# Stepper_Driver_Sheet1.net
KiCad netlist of a schematic drawn in Altium Designer
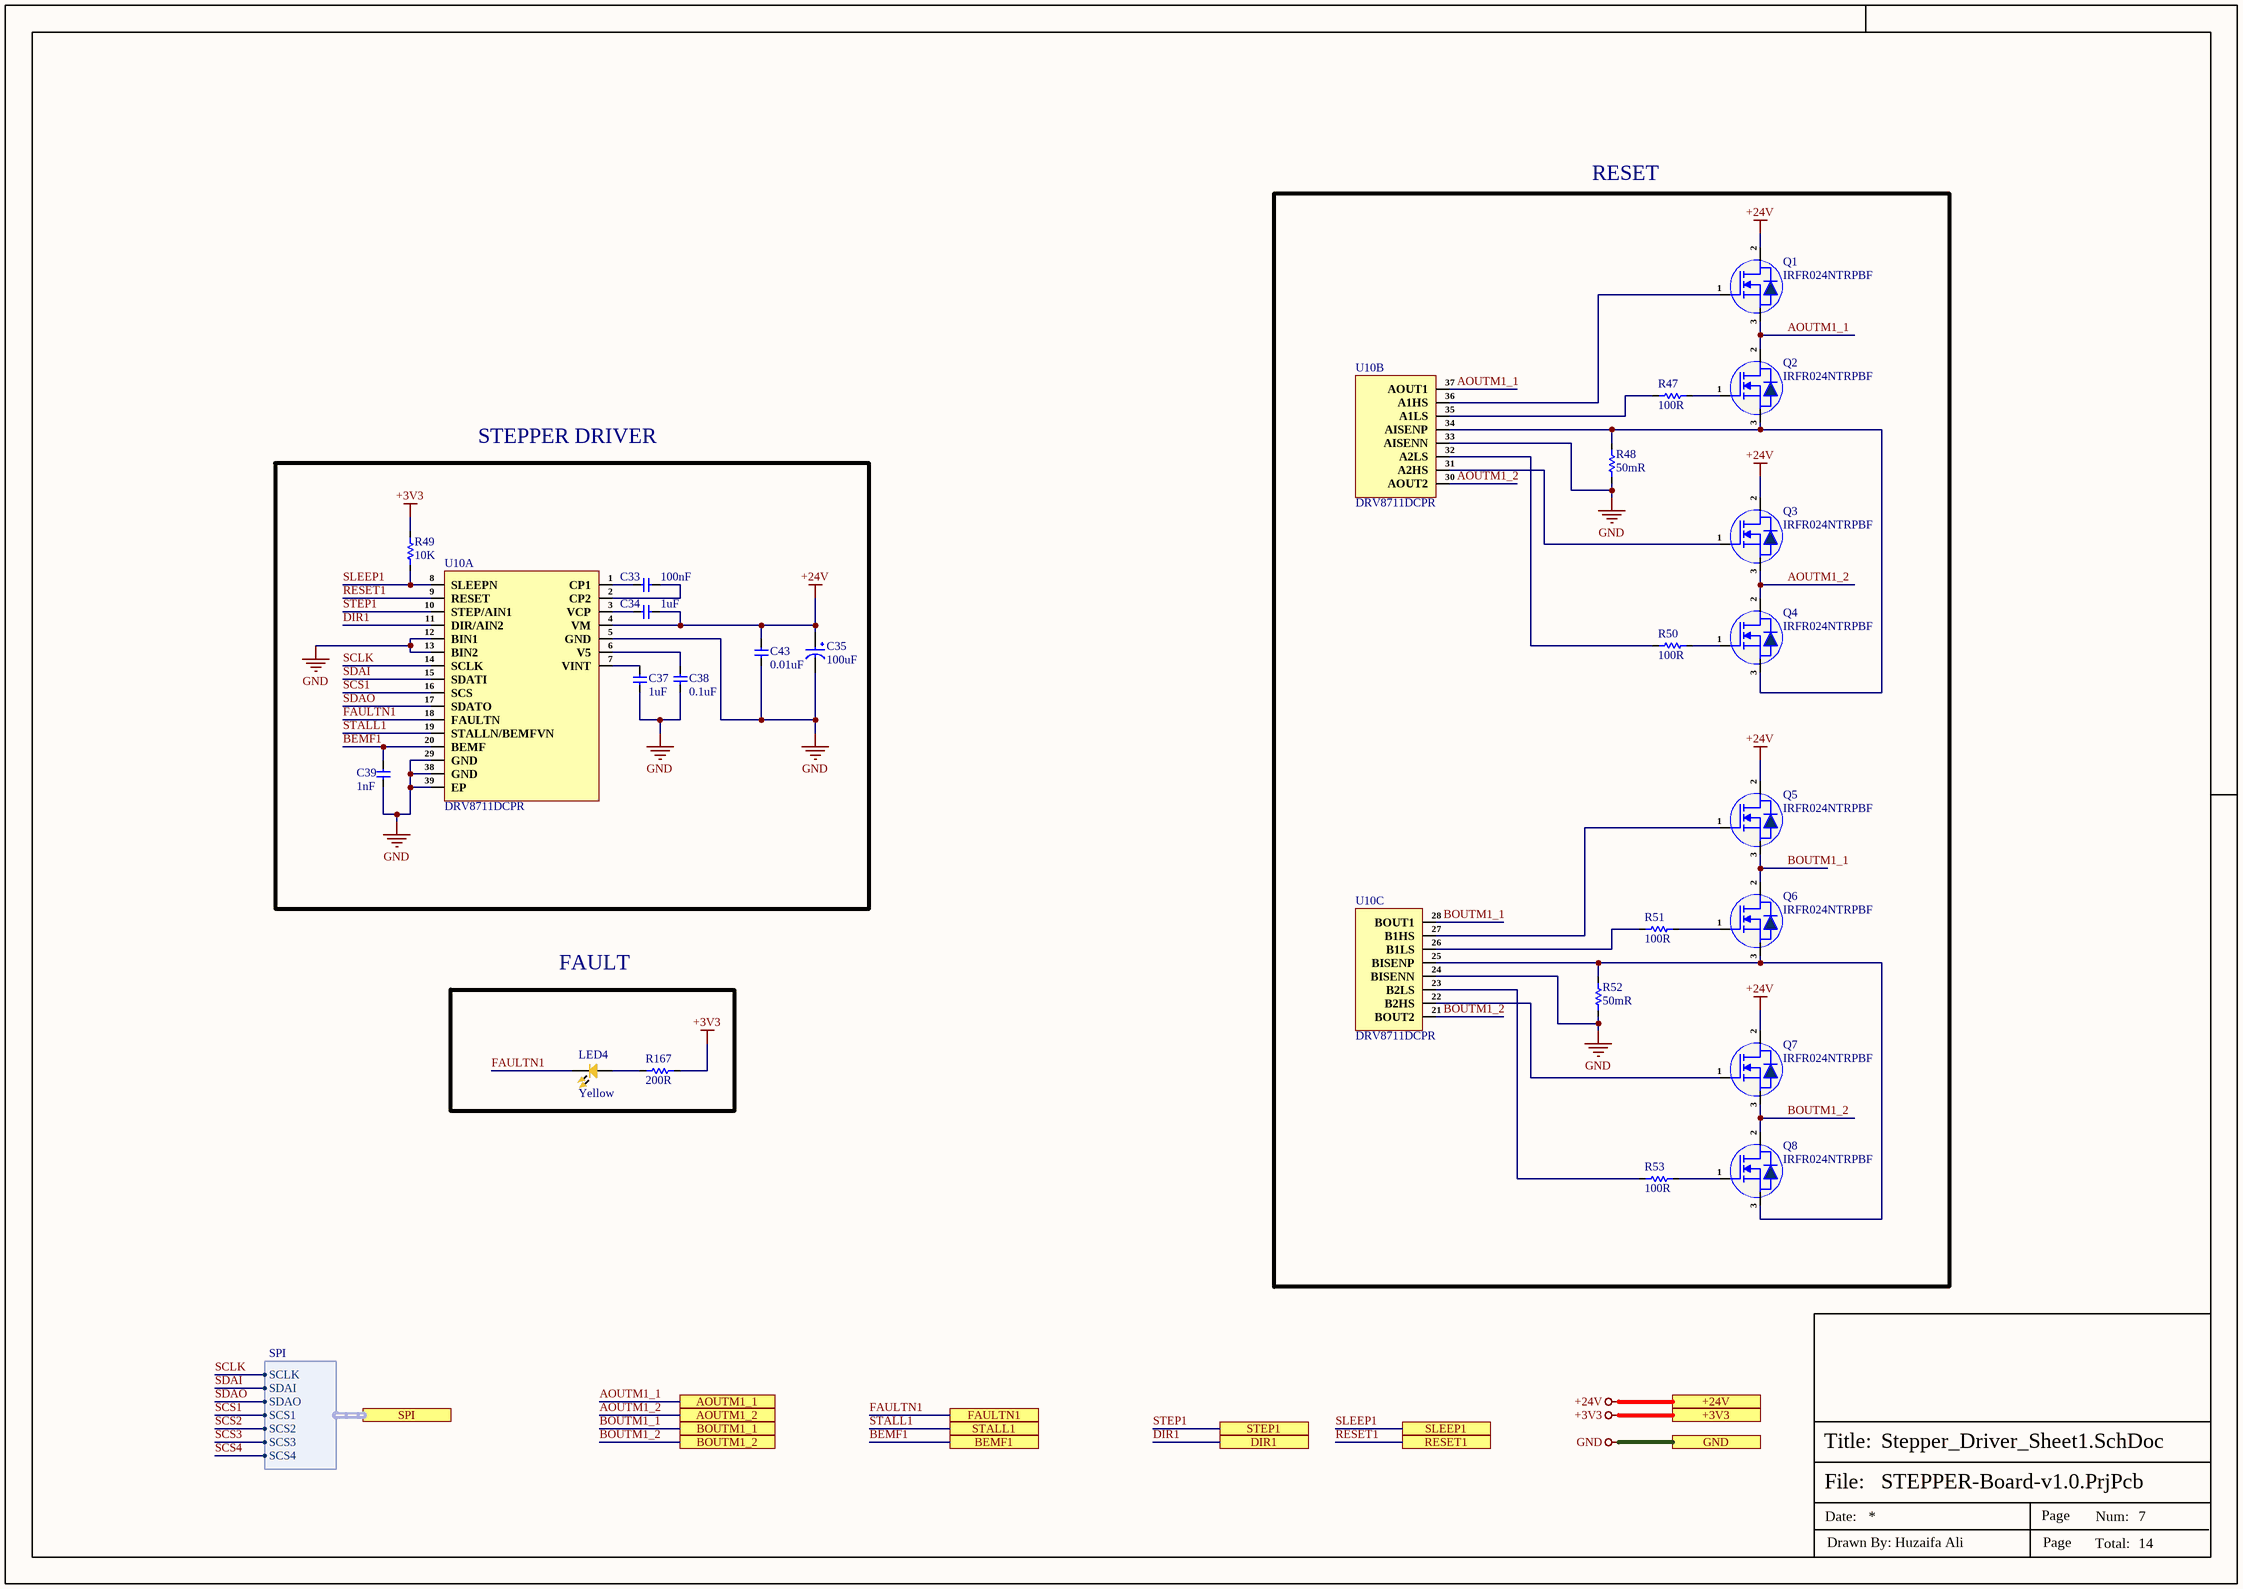
[diagram p0: Stepper_Driver_Sheet1.SchDoc]

(export (version "E")
  (design (tool "Eeschema 10.0.6"))
  (components
    (comp (ref "C33")
      (value "100nF")
      (footprint "cap-0402")
      (description "CAP CER 0.1UF 50V X7R 0402")
      (fields
        (field (name "MANUFACTURER") "TDK")
        (field (name "MANUFACTURER PART NUMBER") "C1005X7R1H104KT000F")
      )
      (libsource (lib "eSpark Libraries") (part "C1005X7R1H104KT000F"))
    )
    (comp (ref "C34")
      (value "1uF")
      (footprint "Cap-0402")
      (description "CAP CER 1UF 10V X5R 0402")
      (fields
        (field (name "MANUFACTURER") "Yageo")
        (field (name "MANUFACTURER PART NUMBER") "CC0402KRX5R6BB105")
      )
      (libsource (lib "eSpark Libraries") (part "CC0402KRX5R6BB105"))
    )
    (comp (ref "C35")
      (value "100uF")
      (footprint "UWT1H101MNL1GS_")
      (description "CAP ALUM 100UF 20% 50V SMD")
      (fields
        (field (name "MANUFACTURER") "Nichicon")
        (field (name "MANUFACTURER PART NUMBER") "UWT1H101MNL1GS")
      )
      (libsource (lib "eSpark Libraries") (part "UWT1H101MNL1GS"))
    )
    (comp (ref "C37")
      (value "1uF")
      (footprint "Cap-0402")
      (description "CAP CER 1UF 10V X5R 0402")
      (fields
        (field (name "MANUFACTURER") "Yageo")
        (field (name "MANUFACTURER PART NUMBER") "CC0402KRX5R6BB105")
      )
      (libsource (lib "eSpark Libraries") (part "CC0402KRX5R6BB105"))
    )
    (comp (ref "C38")
      (value "0.1uF")
      (footprint "Cap-0402")
      (description "CAP CER 0.1UF 16V X7R 0402")
      (fields
        (field (name "MANUFACTURER") "Yageo")
        (field (name "MANUFACTURER PART NUMBER") "CC0402JRX7R7BB104")
      )
      (libsource (lib "eSpark Libraries") (part "CC0402JRX7R7BB104"))
    )
    (comp (ref "C39")
      (value "1nF")
      (footprint "Cap-0402")
      (description "CAP CER 1000PF 25V C0G 0402")
      (fields
        (field (name "MANUFACTURER") "TDK")
        (field (name "MANUFACTURER PART NUMBER") "C1005C0G1E102JT000F")
      )
      (libsource (lib "eSpark Libraries") (part "C1005C0G1E102JT000F"))
    )
    (comp (ref "C43")
      (value "0.01uF")
      (footprint "Cap-0603")
      (description "CAP CER 10000PF 50V C0G/NP0 0603")
      (fields
        (field (name "MANUFACTURER") "Murata")
        (field (name "MANUFACTURER PART NUMBER") "GRM1885C1H103JA01D")
      )
      (libsource (lib "eSpark Libraries") (part "GRM1885C1H103JA01D"))
    )
    (comp (ref "LED4")
      (value "Yellow")
      (footprint "LED-0603")
      (description "yellow 0603 Light Emitting Diodes (LED) ROHS")
      (fields
        (field (name "MANUFACTURER") "Foshan NationStar Optoelectronics")
        (field (name "MANUFACTURER PART NUMBER") "NCD0603Y2")
      )
      (libsource (lib "eSpark Libraries") (part "NCD0603Y2"))
    )
    (comp (ref "Q1")
      (value "IRFR024NTRPBF")
      (footprint "DPAK")
      (description "MOSFET N-CH 55V 17A DPAK")
      (fields (field (name "MANUFACTURER") "Infineon"))
      (libsource (lib "eSpark Libraries") (part "IRFR024NTRPBF"))
    )
    (comp (ref "Q2")
      (value "IRFR024NTRPBF")
      (footprint "DPAK")
      (description "MOSFET N-CH 55V 17A DPAK")
      (fields (field (name "MANUFACTURER") "Infineon"))
      (libsource (lib "eSpark Libraries") (part "IRFR024NTRPBF"))
    )
    (comp (ref "Q3")
      (value "IRFR024NTRPBF")
      (footprint "DPAK")
      (description "MOSFET N-CH 55V 17A DPAK")
      (fields (field (name "MANUFACTURER") "Infineon"))
      (libsource (lib "eSpark Libraries") (part "IRFR024NTRPBF"))
    )
    (comp (ref "Q4")
      (value "IRFR024NTRPBF")
      (footprint "DPAK")
      (description "MOSFET N-CH 55V 17A DPAK")
      (fields (field (name "MANUFACTURER") "Infineon"))
      (libsource (lib "eSpark Libraries") (part "IRFR024NTRPBF"))
    )
    (comp (ref "Q5")
      (value "IRFR024NTRPBF")
      (footprint "DPAK")
      (description "MOSFET N-CH 55V 17A DPAK")
      (fields (field (name "MANUFACTURER") "Infineon"))
      (libsource (lib "eSpark Libraries") (part "IRFR024NTRPBF"))
    )
    (comp (ref "Q6")
      (value "IRFR024NTRPBF")
      (footprint "DPAK")
      (description "MOSFET N-CH 55V 17A DPAK")
      (fields (field (name "MANUFACTURER") "Infineon"))
      (libsource (lib "eSpark Libraries") (part "IRFR024NTRPBF"))
    )
    (comp (ref "Q7")
      (value "IRFR024NTRPBF")
      (footprint "DPAK")
      (description "MOSFET N-CH 55V 17A DPAK")
      (fields (field (name "MANUFACTURER") "Infineon"))
      (libsource (lib "eSpark Libraries") (part "IRFR024NTRPBF"))
    )
    (comp (ref "Q8")
      (value "IRFR024NTRPBF")
      (footprint "DPAK")
      (description "MOSFET N-CH 55V 17A DPAK")
      (fields (field (name "MANUFACTURER") "Infineon"))
      (libsource (lib "eSpark Libraries") (part "IRFR024NTRPBF"))
    )
    (comp (ref "R47")
      (value "100R")
      (footprint "Res-0402")
      (description "RES 100 OHM 1% 1/16W 0402")
      (fields
        (field (name "MANUFACTURER") "Yageo")
        (field (name "MANUFACTURER PART NUMBER") "RC0402FR-07100RL")
      )
      (libsource (lib "eSpark Libraries") (part "RC0402FR-07100RL"))
    )
    (comp (ref "R48")
      (value "50mR")
      (footprint "RES-2010")
      (fields
        (field (name "MANUFACTURER") "TA-I Tech")
        (field (name "MANUFACTURER PART NUMBER") "RLM20FECR050")
        (field (name "LCSC PART NUMBER") "C912938")
      )
      (libsource (lib "eSpark Libraries") (part "RLM20FECR050"))
    )
    (comp (ref "R49")
      (value "10K")
      (footprint "Res-0402")
      (description "RES 10K OHM 1% 1/16W 0402")
      (fields
        (field (name "MANUFACTURER") "Yageo")
        (field (name "MANUFACTURER PART NUMBER") "RC0402FR-0710KL")
      )
      (libsource (lib "eSpark Libraries") (part "RC0402FR-0710KL"))
    )
    (comp (ref "R50")
      (value "100R")
      (footprint "Res-0402")
      (description "RES 100 OHM 1% 1/16W 0402")
      (fields
        (field (name "MANUFACTURER") "Yageo")
        (field (name "MANUFACTURER PART NUMBER") "RC0402FR-07100RL")
      )
      (libsource (lib "eSpark Libraries") (part "RC0402FR-07100RL"))
    )
    (comp (ref "R51")
      (value "100R")
      (footprint "Res-0402")
      (description "RES 100 OHM 1% 1/16W 0402")
      (fields
        (field (name "MANUFACTURER") "Yageo")
        (field (name "MANUFACTURER PART NUMBER") "RC0402FR-07100RL")
      )
      (libsource (lib "eSpark Libraries") (part "RC0402FR-07100RL"))
    )
    (comp (ref "R52")
      (value "50mR")
      (footprint "RES-2010")
      (fields
        (field (name "MANUFACTURER") "TA-I Tech")
        (field (name "MANUFACTURER PART NUMBER") "RLM20FECR050")
        (field (name "LCSC PART NUMBER") "C912938")
      )
      (libsource (lib "eSpark Libraries") (part "RLM20FECR050"))
    )
    (comp (ref "R53")
      (value "100R")
      (footprint "Res-0402")
      (description "RES 100 OHM 1% 1/16W 0402")
      (fields
        (field (name "MANUFACTURER") "Yageo")
        (field (name "MANUFACTURER PART NUMBER") "RC0402FR-07100RL")
      )
      (libsource (lib "eSpark Libraries") (part "RC0402FR-07100RL"))
    )
    (comp (ref "R167")
      (value "200R")
      (footprint "Res-0402")
      (description "RES 200 OHM 1% 1/16W 0402")
      (fields
        (field (name "MANUFACTURER") "Yageo")
        (field (name "MANUFACTURER PART NUMBER") "RC0402FR-07200RL")
      )
      (libsource (lib "eSpark Libraries") (part "RC0402FR-07200RL"))
    )
    (comp (ref "U10")
      (value "DRV8711DCPR")
      (footprint "HTSSOP-38-EP-4.4mm")
      (description "IC MTR DRV BIPOLR 8-52V 38HTSSOP")
      (fields (field (name "LCSC PART NUMBER") "C60013") (field (name "MANUFACTURER") "Texas Instruments"))
      (libsource (lib "") (part "DRV8711DCPR_1"))
    )
  )
  (nets
    (net (code "2") (name "+3V3") (class "Default")
      (node (ref "R167") (pin "2") (pinfunction "2_2") (pintype "passive"))
      (node (ref "R49") (pin "1") (pinfunction "1_1") (pintype "passive"))
    )
    (net (code "3") (name "+24V") (class "Default")
      (node (ref "C34") (pin "2") (pinfunction "2_2") (pintype "passive"))
      (node (ref "C35") (pin "1") (pinfunction "1_1") (pintype "passive"))
      (node (ref "C43") (pin "2") (pinfunction "2_2") (pintype "passive"))
      (node (ref "Q1") (pin "2") (pinfunction "D_2") (pintype "passive"))
      (node (ref "Q3") (pin "2") (pinfunction "D_2") (pintype "passive"))
      (node (ref "Q5") (pin "2") (pinfunction "D_2") (pintype "passive"))
      (node (ref "Q7") (pin "2") (pinfunction "D_2") (pintype "passive"))
      (node (ref "U10") (pin "4") (pinfunction "VM_4") (pintype "passive"))
    )
    (net (code "4") (name "/AOUTM1_1") (class "Default")
      (node (ref "Q1") (pin "3") (pinfunction "S_3") (pintype "passive"))
      (node (ref "Q2") (pin "2") (pinfunction "D_2") (pintype "passive"))
      (node (ref "U10") (pin "37") (pinfunction "AOUT1_37") (pintype "passive"))
    )
    (net (code "5") (name "/AOUTM1_2") (class "Default")
      (node (ref "Q3") (pin "3") (pinfunction "S_3") (pintype "passive"))
      (node (ref "Q4") (pin "2") (pinfunction "D_2") (pintype "passive"))
      (node (ref "U10") (pin "30") (pinfunction "AOUT2_30") (pintype "passive"))
    )
    (net (code "6") (name "/BEMF1") (class "Default")
      (node (ref "C39") (pin "2") (pinfunction "2_2") (pintype "passive"))
      (node (ref "U10") (pin "20") (pinfunction "BEMF_20") (pintype "passive"))
    )
    (net (code "7") (name "/BOUTM1_1") (class "Default")
      (node (ref "Q5") (pin "3") (pinfunction "S_3") (pintype "passive"))
      (node (ref "Q6") (pin "2") (pinfunction "D_2") (pintype "passive"))
      (node (ref "U10") (pin "28") (pinfunction "BOUT1_28") (pintype "passive"))
    )
    (net (code "8") (name "/BOUTM1_2") (class "Default")
      (node (ref "Q7") (pin "3") (pinfunction "S_3") (pintype "passive"))
      (node (ref "Q8") (pin "2") (pinfunction "D_2") (pintype "passive"))
      (node (ref "U10") (pin "21") (pinfunction "BOUT2_21") (pintype "passive"))
    )
    (net (code "9") (name "/DIR1") (class "Default")
      (node (ref "U10") (pin "11") (pinfunction "DIR/AIN2_11") (pintype "passive"))
    )
    (net (code "10") (name "/FAULTN1") (class "Default")
      (node (ref "LED4") (pin "2") (pinfunction "2_2") (pintype "passive"))
      (node (ref "U10") (pin "18") (pinfunction "FAULTN_18") (pintype "passive"))
    )
    (net (code "11") (name "/RESET1") (class "Default")
      (node (ref "U10") (pin "9") (pinfunction "RESET_9") (pintype "passive"))
    )
    (net (code "12") (name "/SCLK") (class "Default")
      (node (ref "U10") (pin "14") (pinfunction "SCLK_14") (pintype "passive"))
    )
    (net (code "13") (name "/SCS1") (class "Default")
      (node (ref "U10") (pin "16") (pinfunction "SCS_16") (pintype "passive"))
    )
    (net (code "17") (name "/SDAI") (class "Default")
      (node (ref "U10") (pin "15") (pinfunction "SDATI_15") (pintype "passive"))
    )
    (net (code "18") (name "/SDAO") (class "Default")
      (node (ref "U10") (pin "17") (pinfunction "SDATO_17") (pintype "passive"))
    )
    (net (code "19") (name "/SLEEP1") (class "Default")
      (node (ref "R49") (pin "2") (pinfunction "2_2") (pintype "passive"))
      (node (ref "U10") (pin "8") (pinfunction "SLEEPN_8") (pintype "passive"))
    )
    (net (code "20") (name "/STALL1") (class "Default")
      (node (ref "U10") (pin "19") (pinfunction "STALLN/BEMFVN_19") (pintype "passive"))
    )
    (net (code "21") (name "/STEP1") (class "Default")
      (node (ref "U10") (pin "10") (pinfunction "STEP/AIN1_10") (pintype "passive"))
    )
    (net (code "23") (name "GND") (class "Default")
      (node (ref "C35") (pin "2") (pinfunction "2_2") (pintype "passive"))
      (node (ref "C37") (pin "1") (pinfunction "1_1") (pintype "passive"))
      (node (ref "C38") (pin "2") (pinfunction "2_2") (pintype "passive"))
      (node (ref "C39") (pin "1") (pinfunction "1_1") (pintype "passive"))
      (node (ref "C43") (pin "1") (pinfunction "1_1") (pintype "passive"))
      (node (ref "R48") (pin "1") (pinfunction "1_1") (pintype "passive"))
      (node (ref "R52") (pin "1") (pinfunction "1_1") (pintype "passive"))
      (node (ref "U10") (pin "12") (pinfunction "BIN1_12") (pintype "passive"))
      (node (ref "U10") (pin "13") (pinfunction "BIN2_13") (pintype "passive"))
      (node (ref "U10") (pin "24") (pinfunction "BISENN_24") (pintype "passive"))
      (node (ref "U10") (pin "29") (pinfunction "GND_29") (pintype "passive"))
      (node (ref "U10") (pin "33") (pinfunction "AISENN_33") (pintype "passive"))
      (node (ref "U10") (pin "38") (pinfunction "GND_38") (pintype "passive"))
      (node (ref "U10") (pin "39") (pinfunction "EP_39") (pintype "passive"))
      (node (ref "U10") (pin "5") (pinfunction "GND_5") (pintype "passive"))
    )
    (net (code "24") (name "Net-(LED4-Pad1)") (class "Default")
      (node (ref "LED4") (pin "1") (pinfunction "1_1") (pintype "passive"))
      (node (ref "R167") (pin "1") (pinfunction "1_1") (pintype "passive"))
    )
    (net (code "25") (name "Net-(Q1-G)") (class "Default")
      (node (ref "Q1") (pin "1") (pinfunction "G_1") (pintype "passive"))
      (node (ref "U10") (pin "36") (pinfunction "A1HS_36") (pintype "passive"))
    )
    (net (code "26") (name "Net-(Q2-G)") (class "Default")
      (node (ref "Q2") (pin "1") (pinfunction "G_1") (pintype "passive"))
      (node (ref "R47") (pin "2") (pinfunction "2_2") (pintype "passive"))
    )
    (net (code "27") (name "Net-(Q2-S)") (class "Default")
      (node (ref "Q2") (pin "3") (pinfunction "S_3") (pintype "passive"))
      (node (ref "Q4") (pin "3") (pinfunction "S_3") (pintype "passive"))
      (node (ref "R48") (pin "2") (pinfunction "2_2") (pintype "passive"))
      (node (ref "U10") (pin "34") (pinfunction "AISENP_34") (pintype "passive"))
    )
    (net (code "28") (name "Net-(Q3-G)") (class "Default")
      (node (ref "Q3") (pin "1") (pinfunction "G_1") (pintype "passive"))
      (node (ref "U10") (pin "31") (pinfunction "A2HS_31") (pintype "passive"))
    )
    (net (code "29") (name "Net-(Q4-G)") (class "Default")
      (node (ref "Q4") (pin "1") (pinfunction "G_1") (pintype "passive"))
      (node (ref "R50") (pin "2") (pinfunction "2_2") (pintype "passive"))
    )
    (net (code "30") (name "Net-(Q5-G)") (class "Default")
      (node (ref "Q5") (pin "1") (pinfunction "G_1") (pintype "passive"))
      (node (ref "U10") (pin "27") (pinfunction "B1HS_27") (pintype "passive"))
    )
    (net (code "31") (name "Net-(Q6-G)") (class "Default")
      (node (ref "Q6") (pin "1") (pinfunction "G_1") (pintype "passive"))
      (node (ref "R51") (pin "2") (pinfunction "2_2") (pintype "passive"))
    )
    (net (code "32") (name "Net-(Q6-S)") (class "Default")
      (node (ref "Q6") (pin "3") (pinfunction "S_3") (pintype "passive"))
      (node (ref "Q8") (pin "3") (pinfunction "S_3") (pintype "passive"))
      (node (ref "R52") (pin "2") (pinfunction "2_2") (pintype "passive"))
      (node (ref "U10") (pin "25") (pinfunction "BISENP_25") (pintype "passive"))
    )
    (net (code "33") (name "Net-(Q7-G)") (class "Default")
      (node (ref "Q7") (pin "1") (pinfunction "G_1") (pintype "passive"))
      (node (ref "U10") (pin "22") (pinfunction "B2HS_22") (pintype "passive"))
    )
    (net (code "34") (name "Net-(Q8-G)") (class "Default")
      (node (ref "Q8") (pin "1") (pinfunction "G_1") (pintype "passive"))
      (node (ref "R53") (pin "2") (pinfunction "2_2") (pintype "passive"))
    )
    (net (code "35") (name "Net-(U10A-CP1)") (class "Default")
      (node (ref "C33") (pin "1") (pinfunction "1_1") (pintype "passive"))
      (node (ref "U10") (pin "1") (pinfunction "CP1_1") (pintype "passive"))
    )
    (net (code "36") (name "Net-(U10A-CP2)") (class "Default")
      (node (ref "C33") (pin "2") (pinfunction "2_2") (pintype "passive"))
      (node (ref "U10") (pin "2") (pinfunction "CP2_2") (pintype "passive"))
    )
    (net (code "37") (name "Net-(U10A-V5)") (class "Default")
      (node (ref "C38") (pin "1") (pinfunction "1_1") (pintype "passive"))
      (node (ref "U10") (pin "6") (pinfunction "V5_6") (pintype "passive"))
    )
    (net (code "38") (name "Net-(U10A-VCP)") (class "Default")
      (node (ref "C34") (pin "1") (pinfunction "1_1") (pintype "passive"))
      (node (ref "U10") (pin "3") (pinfunction "VCP_3") (pintype "passive"))
    )
    (net (code "39") (name "Net-(U10A-VINT)") (class "Default")
      (node (ref "C37") (pin "2") (pinfunction "2_2") (pintype "passive"))
      (node (ref "U10") (pin "7") (pinfunction "VINT_7") (pintype "passive"))
    )
    (net (code "40") (name "Net-(U10B-A1LS)") (class "Default")
      (node (ref "R47") (pin "1") (pinfunction "1_1") (pintype "passive"))
      (node (ref "U10") (pin "35") (pinfunction "A1LS_35") (pintype "passive"))
    )
    (net (code "41") (name "Net-(U10B-A2LS)") (class "Default")
      (node (ref "R50") (pin "1") (pinfunction "1_1") (pintype "passive"))
      (node (ref "U10") (pin "32") (pinfunction "A2LS_32") (pintype "passive"))
    )
    (net (code "42") (name "Net-(U10C-B1LS)") (class "Default")
      (node (ref "R51") (pin "1") (pinfunction "1_1") (pintype "passive"))
      (node (ref "U10") (pin "26") (pinfunction "B1LS_26") (pintype "passive"))
    )
    (net (code "43") (name "Net-(U10C-B2LS)") (class "Default")
      (node (ref "R53") (pin "1") (pinfunction "1_1") (pintype "passive"))
      (node (ref "U10") (pin "23") (pinfunction "B2LS_23") (pintype "passive"))
    )
  )
)
